# 13_-TYPEC0_PROG.net
KiCad netlist of a schematic drawn in Altium Designer
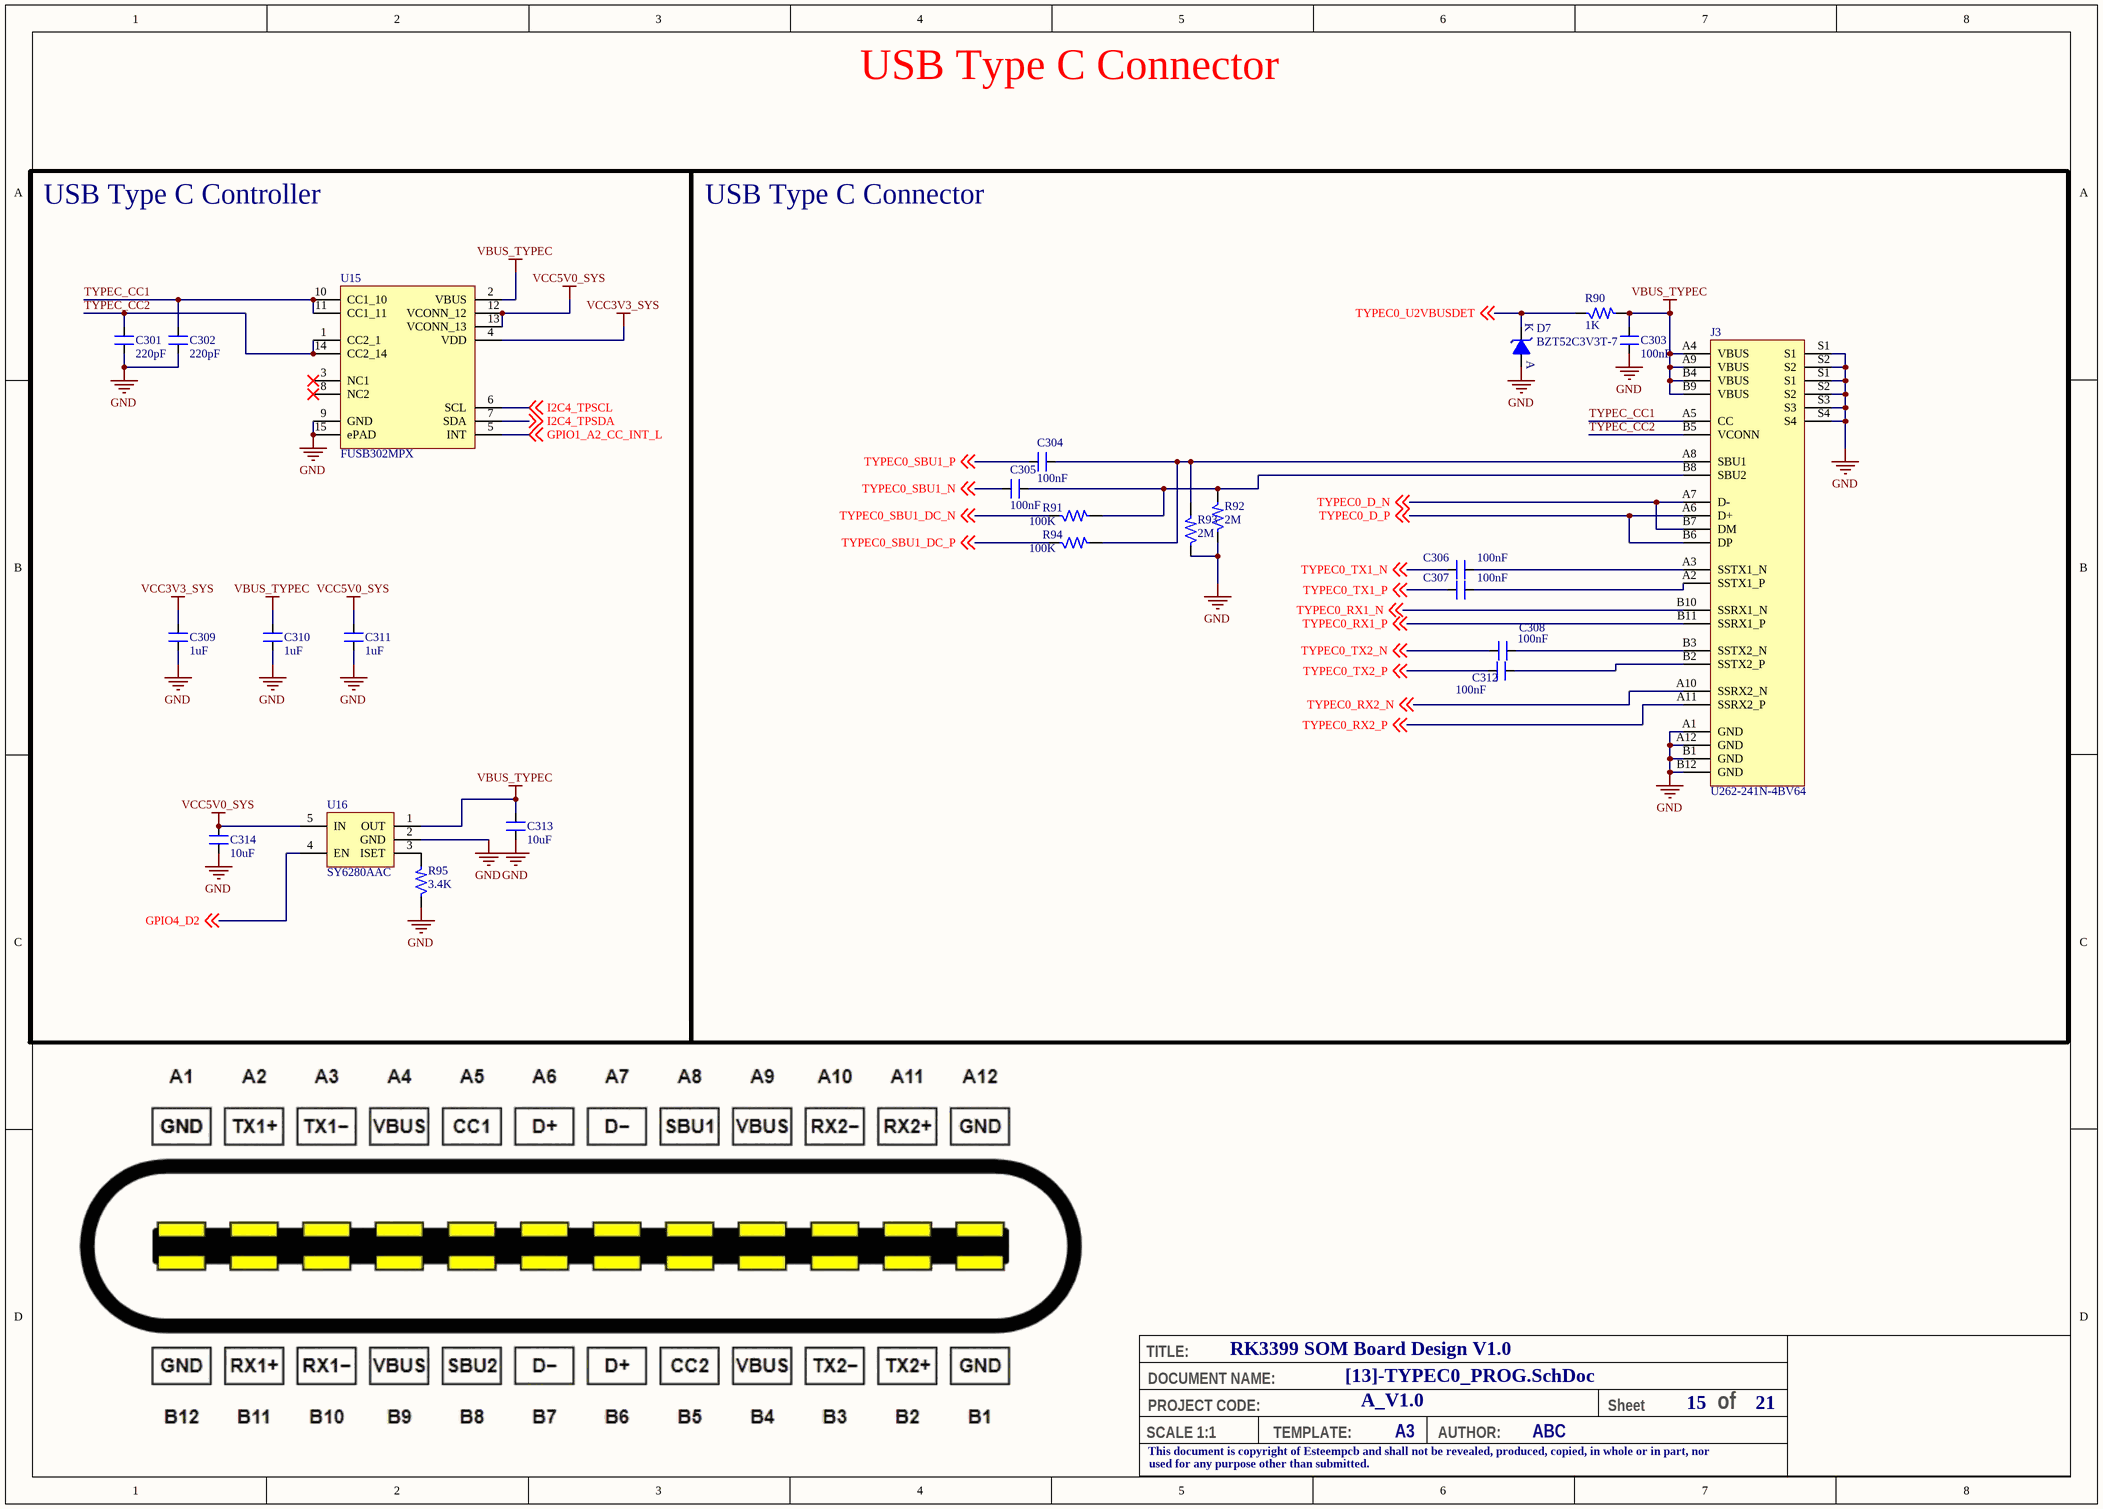
[diagram p0: [13]-TYPEC0_PROG.SchDoc]

(export (version "E")
  (design (tool "Eeschema 10.0.6"))
  (components
    (comp (ref "C301")
      (value "220pF")
      (footprint "CAP_0402")
      (description "220pF ±10% 10V Ceramic Capacitor X7R 0402 (1005 Metric)")
      (fields
        (field (name "MANUFACTURER") "KEMET")
        (field (name "MANUFACTURER PART NUMBER") "C0402C221K8RAC7867")
      )
      (libsource (lib "RK3399 _Module_Schlib") (part "CAP_220pF-10V-10%-0402"))
    )
    (comp (ref "C302")
      (value "220pF")
      (footprint "CAP_0402")
      (description "220pF ±10% 10V Ceramic Capacitor X7R 0402 (1005 Metric)")
      (fields
        (field (name "MANUFACTURER") "KEMET")
        (field (name "MANUFACTURER PART NUMBER") "C0402C221K8RAC7867")
      )
      (libsource (lib "RK3399 _Module_Schlib") (part "CAP_220pF-10V-10%-0402"))
    )
    (comp (ref "C303")
      (value "100nF")
      (footprint "CAP_0603")
      (description "0.1µF ±10% 10V Ceramic Capacitor X7R 0603 (1608 Metric)")
      (fields
        (field (name "MANUFACTURER") "Yageo")
        (field (name "MANUFACTURER PART NUMBER") "CC0603KRX7R6BB104")
      )
      (libsource (lib "RK3399 _Module_Schlib") (part "CAP_100nF-10V-5%-0603"))
    )
    (comp (ref "C304")
      (value "100nF")
      (footprint "CAP_0402")
      (description "0.1µF ±10% 25V Ceramic Capacitor X7R 0402 (1005 Metric)")
      (fields
        (field (name "MANUFACTURER") "Walsin Technology Corporation")
        (field (name "MANUFACTURER PART NUMBER") "0402B104K250CT")
      )
      (libsource (lib "RK3399 _Module_Schlib") (part "CAP_100nF-25V-10%-0402"))
    )
    (comp (ref "C305")
      (value "100nF")
      (footprint "CAP_0402")
      (description "0.1µF ±10% 25V Ceramic Capacitor X7R 0402 (1005 Metric)")
      (fields
        (field (name "MANUFACTURER") "Walsin Technology Corporation")
        (field (name "MANUFACTURER PART NUMBER") "0402B104K250CT")
      )
      (libsource (lib "RK3399 _Module_Schlib") (part "CAP_100nF-25V-10%-0402"))
    )
    (comp (ref "C306")
      (value "100nF")
      (footprint "CAP_0402")
      (description "0.1µF ±10% 25V Ceramic Capacitor X7R 0402 (1005 Metric)")
      (fields
        (field (name "MANUFACTURER") "Walsin Technology Corporation")
        (field (name "MANUFACTURER PART NUMBER") "0402B104K250CT")
      )
      (libsource (lib "RK3399 _Module_Schlib") (part "CAP_100nF-25V-10%-0402"))
    )
    (comp (ref "C307")
      (value "100nF")
      (footprint "CAP_0402")
      (description "0.1µF ±10% 25V Ceramic Capacitor X7R 0402 (1005 Metric)")
      (fields
        (field (name "MANUFACTURER") "Walsin Technology Corporation")
        (field (name "MANUFACTURER PART NUMBER") "0402B104K250CT")
      )
      (libsource (lib "RK3399 _Module_Schlib") (part "CAP_100nF-25V-10%-0402"))
    )
    (comp (ref "C308")
      (value "100nF")
      (footprint "CAP_0402")
      (description "0.1µF ±10% 25V Ceramic Capacitor X7R 0402 (1005 Metric)")
      (fields
        (field (name "MANUFACTURER") "Walsin Technology Corporation")
        (field (name "MANUFACTURER PART NUMBER") "0402B104K250CT")
      )
      (libsource (lib "RK3399 _Module_Schlib") (part "CAP_100nF-25V-10%-0402"))
    )
    (comp (ref "C309")
      (value "1uF")
      (footprint "CAP_0402")
      (description "1µF ±10% 10V Ceramic Capacitor X6S 0402 (1005 Metric)")
      (fields
        (field (name "MANUFACTURER") "Murata Electronics")
        (field (name "MANUFACTURER PART NUMBER") "GRT155C81A105KE01D")
      )
      (libsource (lib "RK3399 _Module_Schlib") (part "CAP_1uF-10V-10%-0402"))
    )
    (comp (ref "C310")
      (value "1uF")
      (footprint "CAP_0402")
      (description "1µF ±10% 10V Ceramic Capacitor X6S 0402 (1005 Metric)")
      (fields
        (field (name "MANUFACTURER") "Murata Electronics")
        (field (name "MANUFACTURER PART NUMBER") "GRT155C81A105KE01D")
      )
      (libsource (lib "RK3399 _Module_Schlib") (part "CAP_1uF-10V-10%-0402"))
    )
    (comp (ref "C311")
      (value "1uF")
      (footprint "CAP_0402")
      (description "1µF ±10% 10V Ceramic Capacitor X6S 0402 (1005 Metric)")
      (fields
        (field (name "MANUFACTURER") "Murata Electronics")
        (field (name "MANUFACTURER PART NUMBER") "GRT155C81A105KE01D")
      )
      (libsource (lib "RK3399 _Module_Schlib") (part "CAP_1uF-10V-10%-0402"))
    )
    (comp (ref "C312")
      (value "100nF")
      (footprint "CAP_0402")
      (description "0.1µF ±10% 25V Ceramic Capacitor X7R 0402 (1005 Metric)")
      (fields
        (field (name "MANUFACTURER") "Walsin Technology Corporation")
        (field (name "MANUFACTURER PART NUMBER") "0402B104K250CT")
      )
      (libsource (lib "RK3399 _Module_Schlib") (part "CAP_100nF-25V-10%-0402"))
    )
    (comp (ref "C313")
      (value "10uF")
      (footprint "CAP_0402")
      (description "10µF ±20% 10V Ceramic Capacitor X5R 0402 (1005 Metric)")
      (fields
        (field (name "MANUFACTURER PART NUMBER") "CL05A106MP5NUNC")
        (field (name "MANUFACTURER") "Samsung Electro-Mechanics")
      )
      (libsource (lib "RK3399 _Module_Schlib") (part "CAP_10uF-10V-20%-0402"))
    )
    (comp (ref "C314")
      (value "10uF")
      (footprint "CAP_0402")
      (description "10µF ±20% 10V Ceramic Capacitor X5R 0402 (1005 Metric)")
      (fields
        (field (name "MANUFACTURER PART NUMBER") "CL05A106MP5NUNC")
        (field (name "MANUFACTURER") "Samsung Electro-Mechanics")
      )
      (libsource (lib "RK3399 _Module_Schlib") (part "CAP_10uF-10V-20%-0402"))
    )
    (comp (ref "D7")
      (value "BZT52C3V3T-7")
      (footprint "DIO_SOD523")
      (description "Zener Diode 3.3V 300mW ±6% Surface Mount SOD-523")
      (fields (field (name "MANUFACTURER") "Diodes Incorporated"))
      (libsource (lib "RK3399 _Module_Schlib") (part "DIO-Z_3.3V-300mW-SOD-523"))
    )
    (comp (ref "J3")
      (value "U262-241N-4BV64")
      (footprint "CON24_19.64_U262-241N-4BV64_TH_RA")
      (description "USB - Type C Female 24 SMD USB Connectors RoHS")
      (fields (field (name "MANUFACTURER") "XKB Connectivity"))
      (libsource (lib "RK3399 _Module_Schlib") (part "CON-TYPEC_U262-241N-4BV64-SMD"))
    )
    (comp (ref "R90")
      (value "1K")
      (footprint "RES_0402")
      (description "1 kOhms ±1% 0.1W, 1/10W Chip Resistor 0402 (1005 Metric) Anti-Sulfur Thin Film")
      (fields
        (field (name "MANUFACTURER") "Vishay Beyschlag/Draloric/BC Components")
        (field (name "MANUFACTURER PART NUMBER") "MCS04020C1001FE000")
      )
      (libsource (lib "RK3399 _Module_Schlib") (part "RES_1K-0.1W-1%-0402"))
    )
    (comp (ref "R91")
      (value "100K")
      (footprint "RES_0402")
      (description "100 kOhms ±1% 0.1W, 1/10W Chip Resistor 0402 (1005 Metric) Anti-Sulfur Thin Film")
      (fields
        (field (name "MANUFACTURER") "Vishay Beyschlag/Draloric/BC Components")
        (field (name "MANUFACTURER PART NUMBER") "MCS04020C1003FE000")
      )
      (libsource (lib "RK3399 _Module_Schlib") (part "RES_100K-0.1W-1%-0402"))
    )
    (comp (ref "R92")
      (value "2M")
      (footprint "RES_0402")
      (description "2 MOhms ±1% 0.1W, 1/10W Chip Resistor 0402 (1005 Metric) Anti-Sulfur Thin Film")
      (fields
        (field (name "MANUFACTURER") "Vishay Beyschlag/Draloric/BC Components")
        (field (name "MANUFACTURER PART NUMBER") "MCS04020C2004FE000")
      )
      (libsource (lib "RK3399 _Module_Schlib") (part "RES_2M-0.1W-1%-0402"))
    )
    (comp (ref "R93")
      (value "2M")
      (footprint "RES_0402")
      (description "2 MOhms ±1% 0.1W, 1/10W Chip Resistor 0402 (1005 Metric) Anti-Sulfur Thin Film")
      (fields
        (field (name "MANUFACTURER") "Vishay Beyschlag/Draloric/BC Components")
        (field (name "MANUFACTURER PART NUMBER") "MCS04020C2004FE000")
      )
      (libsource (lib "RK3399 _Module_Schlib") (part "RES_2M-0.1W-1%-0402"))
    )
    (comp (ref "R94")
      (value "100K")
      (footprint "RES_0402")
      (description "100 kOhms ±1% 0.1W, 1/10W Chip Resistor 0402 (1005 Metric) Anti-Sulfur Thin Film")
      (fields
        (field (name "MANUFACTURER") "Vishay Beyschlag/Draloric/BC Components")
        (field (name "MANUFACTURER PART NUMBER") "MCS04020C1003FE000")
      )
      (libsource (lib "RK3399 _Module_Schlib") (part "RES_100K-0.1W-1%-0402"))
    )
    (comp (ref "R95")
      (value "3.4K")
      (footprint "RES_0402")
      (description "3.4 kOhms ±1% 0.1W, 1/10W Chip Resistor 0402 (1005 Metric) Automotive AEC-Q200 Thick Film")
      (fields
        (field (name "MANUFACTURER") "Panasonic Electronic Components")
        (field (name "MANUFACTURER PART NUMBER") "ERJ-2RKF3401X")
      )
      (libsource (lib "RK3399 _Module_Schlib") (part "RES_3.4K-0.1W-1%-0402"))
    )
    (comp (ref "U15")
      (value "FUSB302MPX")
      (footprint "MLP-14_98.4X98.4_SMD")
      (description "USB Controller USB 3.1 USB Interface 14-MLP (2.5x2.5)")
      (fields (field (name "MANUFACTURER") "ON Semiconductor"))
      (libsource (lib "RK3399 _Module_Schlib") (part "IC_FUSB302MPX"))
    )
    (comp (ref "U16")
      (value "SY6280AAC")
      (footprint "SOT23-5")
      (description "SOT-23-5 PMIC - Power Distribution Switches RoHS")
      (fields (field (name "MANUFACTURER") "Silergy Corp"))
      (libsource (lib "RK3399 _Module_Schlib") (part "REG-ADJ_5.5V-5.5V-1.25A-SOT-23-5"))
    )
  )
  (nets
    (net (code "1") (name "/TYPEC_CC1") (class "Default")
      (node (ref "C302") (pin "2") (pinfunction "2_2") (pintype "passive"))
      (node (ref "J3") (pin "A5") (pinfunction "CC_A5") (pintype "passive"))
      (node (ref "U15") (pin "10") (pinfunction "CC1_10_10") (pintype "passive"))
      (node (ref "U15") (pin "11") (pinfunction "CC1_11_11") (pintype "passive"))
    )
    (net (code "2") (name "/TYPEC_CC2") (class "Default")
      (node (ref "C301") (pin "2") (pinfunction "2_2") (pintype "passive"))
      (node (ref "J3") (pin "B5") (pinfunction "VCONN_B5") (pintype "passive"))
      (node (ref "U15") (pin "1") (pinfunction "CC2_1_1") (pintype "passive"))
      (node (ref "U15") (pin "14") (pinfunction "CC2_14_14") (pintype "passive"))
    )
    (net (code "3") (name "GND") (class "Default")
      (node (ref "C301") (pin "1") (pinfunction "1_1") (pintype "passive"))
      (node (ref "C302") (pin "1") (pinfunction "1_1") (pintype "passive"))
      (node (ref "C303") (pin "1") (pinfunction "1_1") (pintype "passive"))
      (node (ref "C309") (pin "1") (pinfunction "1_1") (pintype "passive"))
      (node (ref "C310") (pin "1") (pinfunction "1_1") (pintype "passive"))
      (node (ref "C311") (pin "1") (pinfunction "1_1") (pintype "passive"))
      (node (ref "C313") (pin "1") (pinfunction "1_1") (pintype "passive"))
      (node (ref "C314") (pin "1") (pinfunction "1_1") (pintype "passive"))
      (node (ref "D7") (pin "A") (pinfunction "A_A") (pintype "passive"))
      (node (ref "J3") (pin "A1") (pinfunction "GND_A1") (pintype "passive"))
      (node (ref "J3") (pin "A12") (pinfunction "GND_A12") (pintype "passive"))
      (node (ref "J3") (pin "B1") (pinfunction "GND_B1") (pintype "passive"))
      (node (ref "J3") (pin "B12") (pinfunction "GND_B12") (pintype "passive"))
      (node (ref "J3") (pin "S1") (pinfunction "S1_S1") (pintype "passive"))
      (node (ref "J3") (pin "S2") (pinfunction "S2_S2") (pintype "passive"))
      (node (ref "J3") (pin "S3") (pinfunction "S3_S3") (pintype "passive"))
      (node (ref "J3") (pin "S4") (pinfunction "S4_S4") (pintype "passive"))
      (node (ref "R92") (pin "1") (pinfunction "1_1") (pintype "passive"))
      (node (ref "R93") (pin "1") (pinfunction "1_1") (pintype "passive"))
      (node (ref "R95") (pin "1") (pinfunction "1_1") (pintype "passive"))
      (node (ref "U15") (pin "15") (pinfunction "ePAD_15") (pintype "passive"))
      (node (ref "U15") (pin "9") (pinfunction "GND_9") (pintype "passive"))
      (node (ref "U16") (pin "2") (pinfunction "GND_2") (pintype "passive"))
    )
    (net (code "4") (name "GPIO1_A2_CC_INT_L") (class "Default")
      (node (ref "U15") (pin "5") (pinfunction "INT_5") (pintype "passive"))
    )
    (net (code "5") (name "GPIO4_D2") (class "Default")
      (node (ref "U16") (pin "4") (pinfunction "EN_4") (pintype "passive"))
    )
    (net (code "6") (name "I2C4_TPSCL") (class "Default")
      (node (ref "U15") (pin "6") (pinfunction "SCL_6") (pintype "passive"))
    )
    (net (code "7") (name "I2C4_TPSDA") (class "Default")
      (node (ref "U15") (pin "7") (pinfunction "SDA_7") (pintype "passive"))
    )
    (net (code "8") (name "Net-(J3-SBU1)") (class "Default")
      (node (ref "C304") (pin "2") (pinfunction "2_2") (pintype "passive"))
      (node (ref "J3") (pin "A8") (pinfunction "SBU1_A8") (pintype "passive"))
      (node (ref "R93") (pin "2") (pinfunction "2_2") (pintype "passive"))
      (node (ref "R94") (pin "2") (pinfunction "2_2") (pintype "passive"))
    )
    (net (code "9") (name "Net-(J3-SBU2)") (class "Default")
      (node (ref "C305") (pin "2") (pinfunction "2_2") (pintype "passive"))
      (node (ref "J3") (pin "B8") (pinfunction "SBU2_B8") (pintype "passive"))
      (node (ref "R91") (pin "2") (pinfunction "2_2") (pintype "passive"))
      (node (ref "R92") (pin "2") (pinfunction "2_2") (pintype "passive"))
    )
    (net (code "10") (name "Net-(J3-SSTX1_N)") (class "Default")
      (node (ref "C306") (pin "2") (pinfunction "2_2") (pintype "passive"))
      (node (ref "J3") (pin "A3") (pinfunction "SSTX1_N_A3") (pintype "passive"))
    )
    (net (code "11") (name "Net-(J3-SSTX1_P)") (class "Default")
      (node (ref "C307") (pin "2") (pinfunction "2_2") (pintype "passive"))
      (node (ref "J3") (pin "A2") (pinfunction "SSTX1_P_A2") (pintype "passive"))
    )
    (net (code "12") (name "Net-(J3-SSTX2_N)") (class "Default")
      (node (ref "C308") (pin "2") (pinfunction "2_2") (pintype "passive"))
      (node (ref "J3") (pin "B3") (pinfunction "SSTX2_N_B3") (pintype "passive"))
    )
    (net (code "13") (name "Net-(J3-SSTX2_P)") (class "Default")
      (node (ref "C312") (pin "2") (pinfunction "2_2") (pintype "passive"))
      (node (ref "J3") (pin "B2") (pinfunction "SSTX2_P_B2") (pintype "passive"))
    )
    (net (code "14") (name "Net-(U16-ISET)") (class "Default")
      (node (ref "R95") (pin "2") (pinfunction "2_2") (pintype "passive"))
      (node (ref "U16") (pin "3") (pinfunction "ISET_3") (pintype "passive"))
    )
    (net (code "15") (name "TYPEC0_D_N") (class "Default")
      (node (ref "J3") (pin "A7") (pinfunction "D-_A7") (pintype "passive"))
      (node (ref "J3") (pin "B7") (pinfunction "DM_B7") (pintype "passive"))
    )
    (net (code "16") (name "TYPEC0_D_P") (class "Default")
      (node (ref "J3") (pin "A6") (pinfunction "D+_A6") (pintype "passive"))
      (node (ref "J3") (pin "B6") (pinfunction "DP_B6") (pintype "passive"))
    )
    (net (code "17") (name "TYPEC0_RX1_N") (class "Default")
      (node (ref "J3") (pin "B10") (pinfunction "SSRX1_N_B10") (pintype "passive"))
    )
    (net (code "18") (name "TYPEC0_RX1_P") (class "Default")
      (node (ref "J3") (pin "B11") (pinfunction "SSRX1_P_B11") (pintype "passive"))
    )
    (net (code "19") (name "TYPEC0_RX2_N") (class "Default")
      (node (ref "J3") (pin "A10") (pinfunction "SSRX2_N_A10") (pintype "passive"))
    )
    (net (code "20") (name "TYPEC0_RX2_P") (class "Default")
      (node (ref "J3") (pin "A11") (pinfunction "SSRX2_P_A11") (pintype "passive"))
    )
    (net (code "21") (name "TYPEC0_SBU1_DC_N") (class "Default")
      (node (ref "R91") (pin "1") (pinfunction "1_1") (pintype "passive"))
    )
    (net (code "22") (name "TYPEC0_SBU1_DC_P") (class "Default")
      (node (ref "R94") (pin "1") (pinfunction "1_1") (pintype "passive"))
    )
    (net (code "23") (name "TYPEC0_SBU1_N") (class "Default")
      (node (ref "C305") (pin "1") (pinfunction "1_1") (pintype "passive"))
    )
    (net (code "24") (name "TYPEC0_SBU1_P") (class "Default")
      (node (ref "C304") (pin "1") (pinfunction "1_1") (pintype "passive"))
    )
    (net (code "25") (name "TYPEC0_TX1_N") (class "Default")
      (node (ref "C306") (pin "1") (pinfunction "1_1") (pintype "passive"))
    )
    (net (code "26") (name "TYPEC0_TX1_P") (class "Default")
      (node (ref "C307") (pin "1") (pinfunction "1_1") (pintype "passive"))
    )
    (net (code "27") (name "TYPEC0_TX2_N") (class "Default")
      (node (ref "C308") (pin "1") (pinfunction "1_1") (pintype "passive"))
    )
    (net (code "28") (name "TYPEC0_TX2_P") (class "Default")
      (node (ref "C312") (pin "1") (pinfunction "1_1") (pintype "passive"))
    )
    (net (code "29") (name "TYPEC0_U2VBUSDET") (class "Default")
      (node (ref "D7") (pin "K") (pinfunction "K_K") (pintype "passive"))
      (node (ref "R90") (pin "1") (pinfunction "1_1") (pintype "passive"))
    )
    (net (code "30") (name "VBUS_TYPEC") (class "Default")
      (node (ref "C303") (pin "2") (pinfunction "2_2") (pintype "passive"))
      (node (ref "C310") (pin "2") (pinfunction "2_2") (pintype "passive"))
      (node (ref "C313") (pin "2") (pinfunction "2_2") (pintype "passive"))
      (node (ref "J3") (pin "A4") (pinfunction "VBUS_A4") (pintype "passive"))
      (node (ref "J3") (pin "A9") (pinfunction "VBUS_A9") (pintype "passive"))
      (node (ref "J3") (pin "B4") (pinfunction "VBUS_B4") (pintype "passive"))
      (node (ref "J3") (pin "B9") (pinfunction "VBUS_B9") (pintype "passive"))
      (node (ref "R90") (pin "2") (pinfunction "2_2") (pintype "passive"))
      (node (ref "U15") (pin "2") (pinfunction "VBUS_2") (pintype "passive"))
      (node (ref "U16") (pin "1") (pinfunction "OUT_1") (pintype "passive"))
    )
    (net (code "31") (name "VCC3V3_SYS") (class "Default")
      (node (ref "C309") (pin "2") (pinfunction "2_2") (pintype "passive"))
      (node (ref "U15") (pin "4") (pinfunction "VDD_4") (pintype "passive"))
    )
    (net (code "32") (name "VCC5V0_SYS") (class "Default")
      (node (ref "C311") (pin "2") (pinfunction "2_2") (pintype "passive"))
      (node (ref "C314") (pin "2") (pinfunction "2_2") (pintype "passive"))
      (node (ref "U15") (pin "12") (pinfunction "VCONN_12_12") (pintype "passive"))
      (node (ref "U15") (pin "13") (pinfunction "VCONN_13_13") (pintype "passive"))
      (node (ref "U16") (pin "5") (pinfunction "IN_5") (pintype "passive"))
    )
    (net (code "33") (name "unconnected-(U15-NC1-Pad3)") (class "Default")
      (node (ref "U15") (pin "3") (pinfunction "NC1_3") (pintype "passive+no_connect"))
    )
    (net (code "34") (name "unconnected-(U15-NC2-Pad8)") (class "Default")
      (node (ref "U15") (pin "8") (pinfunction "NC2_8") (pintype "passive+no_connect"))
    )
  )
)
